# Sheet1.net
KiCad netlist of a schematic drawn in Altium Designer
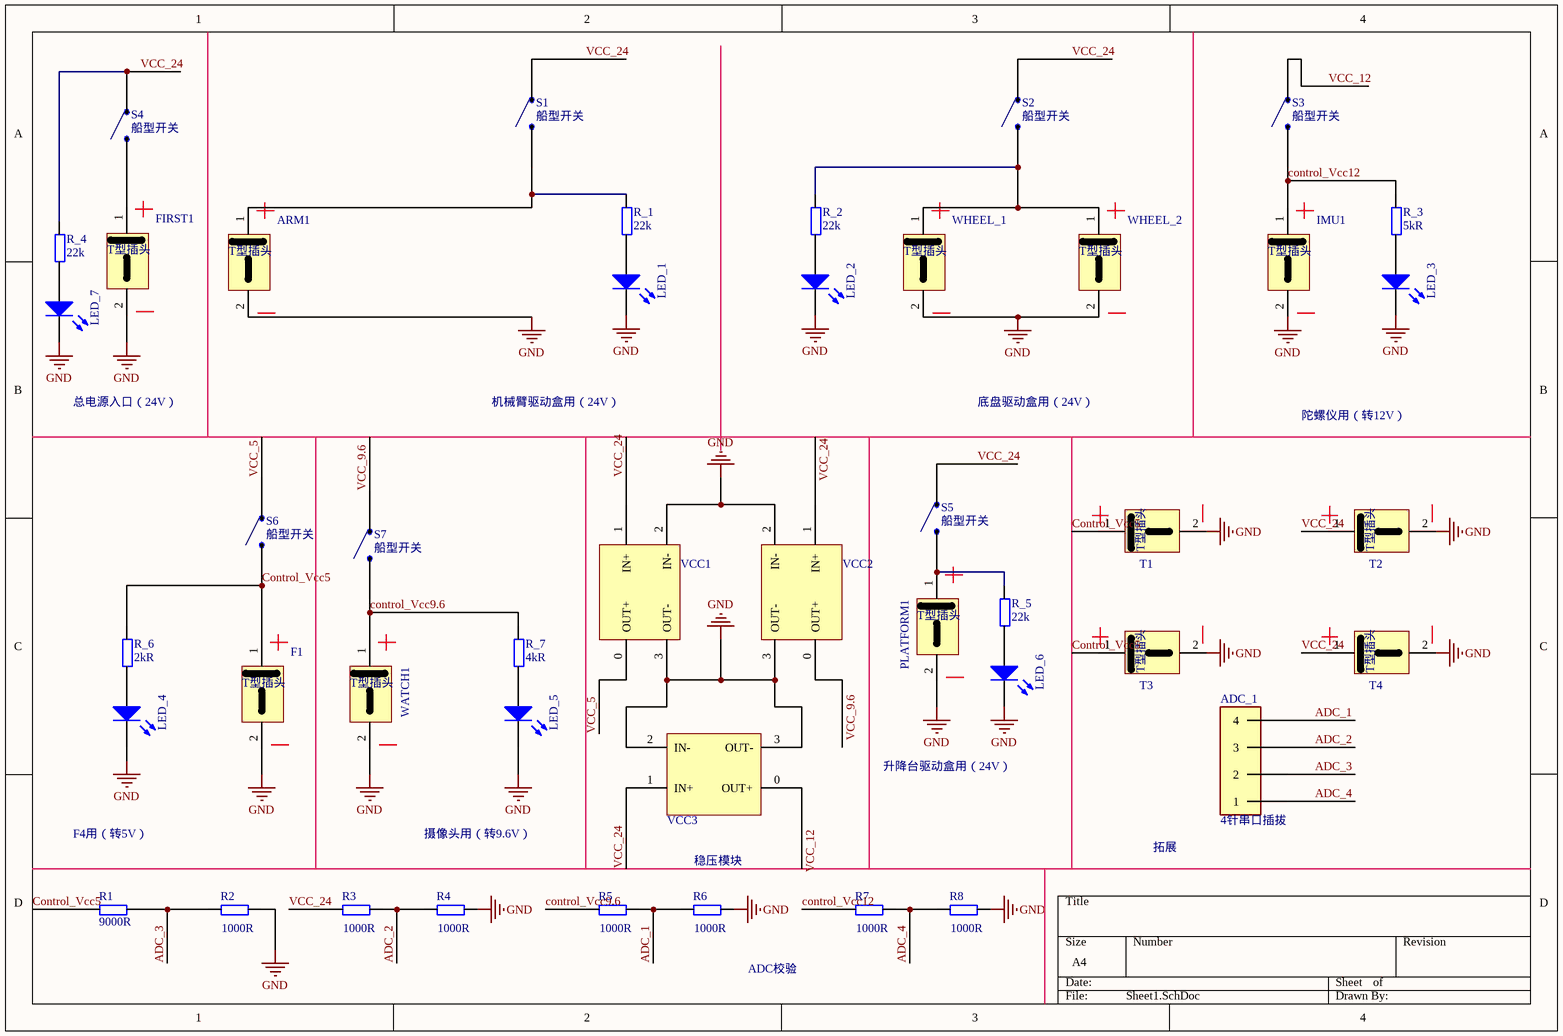
[diagram p0: Sheet1.SchDoc]

(export (version "E")
  (design (tool "Eeschema 10.0.6"))
  (components
    (comp (ref "ADC_1")
      (value "4针串口插拔")
      (footprint "HDR_4针串口插拔")
      (libsource (lib "PCB_PROJECT1") (part "4针串口插拔"))
    )
    (comp (ref "ARM1")
      (value "T型插头_WYN")
      (footprint "HDR_XT60")
      (libsource (lib "PCB_PROJECT1") (part "T型插头_WYN"))
    )
    (comp (ref "F1")
      (value "T型插头_WYN")
      (footprint "HDR_XT30")
      (libsource (lib "PCB_PROJECT1") (part "T型插头_WYN"))
    )
    (comp (ref "FIRST1")
      (value "T型插头_WYN")
      (footprint "HDR_XT60")
      (libsource (lib "PCB_PROJECT1") (part "T型插头_WYN"))
    )
    (comp (ref "IMU1")
      (value "T型插头_WYN")
      (footprint "HDR_XT30")
      (libsource (lib "PCB_PROJECT1") (part "T型插头_WYN"))
    )
    (comp (ref "LED_1")
      (value "LED")
      (footprint "ELE_SMDLED")
      (description "Typical RED, GREEN, YELLOW, AMBER GaAs LED")
      (fields (field (name "PUBLISHER") "Altium Limited"))
      (libsource (lib "PCB_PROJECT1") (part "LED2"))
    )
    (comp (ref "LED_2")
      (value "LED")
      (footprint "ELE_SMDLED")
      (description "Typical RED, GREEN, YELLOW, AMBER GaAs LED")
      (fields (field (name "PUBLISHER") "Altium Limited"))
      (libsource (lib "PCB_PROJECT1") (part "LED2"))
    )
    (comp (ref "LED_3")
      (value "LED")
      (footprint "ELE_SMDLED")
      (description "Typical RED, GREEN, YELLOW, AMBER GaAs LED")
      (fields (field (name "PUBLISHER") "Altium Limited"))
      (libsource (lib "PCB_PROJECT1") (part "LED2"))
    )
    (comp (ref "LED_4")
      (value "LED")
      (footprint "ELE_SMDLED")
      (description "Typical RED, GREEN, YELLOW, AMBER GaAs LED")
      (fields (field (name "PUBLISHER") "Altium Limited"))
      (libsource (lib "PCB_PROJECT1") (part "LED2"))
    )
    (comp (ref "LED_5")
      (value "LED")
      (footprint "ELE_SMDLED")
      (description "Typical RED, GREEN, YELLOW, AMBER GaAs LED")
      (fields (field (name "PUBLISHER") "Altium Limited"))
      (libsource (lib "PCB_PROJECT1") (part "LED2"))
    )
    (comp (ref "LED_6")
      (value "LED")
      (footprint "ELE_SMDLED")
      (description "Typical RED, GREEN, YELLOW, AMBER GaAs LED")
      (fields (field (name "PUBLISHER") "Altium Limited"))
      (libsource (lib "PCB_PROJECT1") (part "LED2"))
    )
    (comp (ref "LED_7")
      (value "LED")
      (footprint "ELE_SMDLED")
      (description "Typical RED, GREEN, YELLOW, AMBER GaAs LED")
      (fields (field (name "PUBLISHER") "Altium Limited"))
      (libsource (lib "PCB_PROJECT1") (part "LED2"))
    )
    (comp (ref "PLATFORM1")
      (value "T型插头_WYN")
      (footprint "HDR_XT60")
      (libsource (lib "PCB_PROJECT1") (part "T型插头_WYN"))
    )
    (comp (ref "R1") (value "9000R") (footprint "ELE_0603_P") (libsource (lib "PCB_PROJECT1") (part "R")))
    (comp (ref "R2") (value "1000R") (footprint "ELE_0603_P") (libsource (lib "PCB_PROJECT1") (part "R")))
    (comp (ref "R3") (value "1000R") (footprint "ELE_0603_P") (libsource (lib "PCB_PROJECT1") (part "R")))
    (comp (ref "R4") (value "1000R") (footprint "ELE_0603_P") (libsource (lib "PCB_PROJECT1") (part "R")))
    (comp (ref "R5") (value "1000R") (footprint "ELE_0603_P") (libsource (lib "PCB_PROJECT1") (part "R")))
    (comp (ref "R6") (value "1000R") (footprint "ELE_0603_P") (libsource (lib "PCB_PROJECT1") (part "R")))
    (comp (ref "R7") (value "1000R") (footprint "ELE_0603_P") (libsource (lib "PCB_PROJECT1") (part "R")))
    (comp (ref "R8") (value "1000R") (footprint "ELE_0603_P") (libsource (lib "PCB_PROJECT1") (part "R")))
    (comp (ref "R_1") (value "22k") (footprint "ELE_0603_P") (libsource (lib "PCB_PROJECT1") (part "R")))
    (comp (ref "R_2") (value "22k") (footprint "ELE_0603_P") (libsource (lib "PCB_PROJECT1") (part "R")))
    (comp (ref "R_3") (value "5kR") (footprint "ELE_0603_P") (libsource (lib "PCB_PROJECT1") (part "R")))
    (comp (ref "R_4") (value "22k") (footprint "ELE_0603_P") (libsource (lib "PCB_PROJECT1") (part "R")))
    (comp (ref "R_5") (value "22k") (footprint "ELE_0603_P") (libsource (lib "PCB_PROJECT1") (part "R")))
    (comp (ref "R_6") (value "2kR") (footprint "ELE_0603_P") (libsource (lib "PCB_PROJECT1") (part "R")))
    (comp (ref "R_7") (value "4kR") (footprint "ELE_0603_P") (libsource (lib "PCB_PROJECT1") (part "R")))
    (comp (ref "S1") (value "船型开关") (footprint "ELE_船型开关") (libsource (lib "PCB_PROJECT1") (part "船型开关")))
    (comp (ref "S2") (value "船型开关") (footprint "ELE_船型开关") (libsource (lib "PCB_PROJECT1") (part "船型开关")))
    (comp (ref "S3") (value "船型开关") (footprint "ELE_船型开关1_D") (libsource (lib "PCB_PROJECT1") (part "船型开关")))
    (comp (ref "S4") (value "船型开关") (footprint "ELE_船型开关") (libsource (lib "PCB_PROJECT1") (part "船型开关")))
    (comp (ref "S5") (value "船型开关") (footprint "ELE_船型开关") (libsource (lib "PCB_PROJECT1") (part "船型开关")))
    (comp (ref "S6") (value "船型开关") (footprint "ELE_船型开关1_D") (libsource (lib "PCB_PROJECT1") (part "船型开关")))
    (comp (ref "S7") (value "船型开关") (footprint "ELE_船型开关1_D") (libsource (lib "PCB_PROJECT1") (part "船型开关")))
    (comp (ref "T1") (value "T型插头_WYN") (footprint "HDR_XT30") (libsource (lib "") (part "T型插头_WYN_1")))
    (comp (ref "T2") (value "T型插头_WYN") (footprint "HDR_XT60") (libsource (lib "") (part "T型插头_WYN_1")))
    (comp (ref "T3") (value "T型插头_WYN") (footprint "HDR_XT30") (libsource (lib "") (part "T型插头_WYN_1")))
    (comp (ref "T4") (value "T型插头_WYN") (footprint "HDR_XT60") (libsource (lib "") (part "T型插头_WYN_1")))
    (comp (ref "VCC1")
      (value "TRANSFORM")
      (footprint "CHP_转压模块")
      (libsource (lib "PCB_PROJECT1") (part "TRANSFORM"))
    )
    (comp (ref "VCC2") (value "TRANSFORM") (footprint "CHP_转压模块") (libsource (lib "") (part "TRANSFORM_1")))
    (comp (ref "VCC3") (value "TRANSFORM") (footprint "CHP_转压模块") (libsource (lib "") (part "TRANSFORM_2")))
    (comp (ref "WATCH1")
      (value "T型插头_WYN")
      (footprint "HDR_XT30")
      (libsource (lib "PCB_PROJECT1") (part "T型插头_WYN"))
    )
    (comp (ref "WHEEL_1")
      (value "T型插头_WYN")
      (footprint "HDR_XT60")
      (libsource (lib "PCB_PROJECT1") (part "T型插头_WYN"))
    )
    (comp (ref "WHEEL_2")
      (value "T型插头_WYN")
      (footprint "HDR_XT60")
      (libsource (lib "PCB_PROJECT1") (part "T型插头_WYN"))
    )
  )
  (nets
    (net (code "1") (name "/ADC_1") (class "Default")
      (node (ref "ADC_1") (pin "4") (pinfunction "4_4") (pintype "passive"))
      (node (ref "R5") (pin "2") (pintype "passive"))
      (node (ref "R6") (pin "1") (pintype "passive"))
    )
    (net (code "2") (name "/ADC_2") (class "Default")
      (node (ref "ADC_1") (pin "3") (pinfunction "3_3") (pintype "passive"))
      (node (ref "R3") (pin "2") (pintype "passive"))
      (node (ref "R4") (pin "1") (pintype "passive"))
    )
    (net (code "3") (name "/ADC_3") (class "Default")
      (node (ref "ADC_1") (pin "2") (pinfunction "2_2") (pintype "passive"))
      (node (ref "R1") (pin "2") (pintype "passive"))
      (node (ref "R2") (pin "1") (pintype "passive"))
    )
    (net (code "4") (name "/ADC_4") (class "Default")
      (node (ref "ADC_1") (pin "1") (pinfunction "1_1") (pintype "passive"))
      (node (ref "R7") (pin "2") (pintype "passive"))
      (node (ref "R8") (pin "1") (pintype "passive"))
    )
    (net (code "5") (name "/Control_Vcc5") (class "Default")
      (node (ref "F1") (pin "1") (pinfunction "1_1") (pintype "passive"))
      (node (ref "R1") (pin "1") (pintype "passive"))
      (node (ref "R_6") (pin "2") (pintype "passive"))
      (node (ref "S6") (pin "1") (pinfunction "1_1") (pintype "passive"))
      (node (ref "T1") (pin "1") (pinfunction "1_1") (pintype "passive"))
      (node (ref "T3") (pin "1") (pinfunction "1_1") (pintype "passive"))
    )
    (net (code "6") (name "/VCC_5") (class "Default")
      (node (ref "S6") (pin "2") (pinfunction "2_2") (pintype "passive"))
      (node (ref "VCC1") (pin "0") (pinfunction "OUT+_0") (pintype "passive"))
    )
    (net (code "7") (name "/VCC_9.6") (class "Default")
      (node (ref "S7") (pin "2") (pinfunction "2_2") (pintype "passive"))
      (node (ref "VCC2") (pin "0") (pinfunction "OUT+_0") (pintype "passive"))
    )
    (net (code "8") (name "/VCC_12") (class "Default")
      (node (ref "S3") (pin "2") (pinfunction "2_2") (pintype "passive"))
      (node (ref "VCC3") (pin "0") (pinfunction "OUT+_0") (pintype "passive"))
    )
    (net (code "9") (name "/VCC_24") (class "Default")
      (node (ref "R3") (pin "1") (pintype "passive"))
      (node (ref "R_4") (pin "2") (pintype "passive"))
      (node (ref "S1") (pin "2") (pinfunction "2_2") (pintype "passive"))
      (node (ref "S2") (pin "2") (pinfunction "2_2") (pintype "passive"))
      (node (ref "S4") (pin "2") (pinfunction "2_2") (pintype "passive"))
      (node (ref "S5") (pin "2") (pinfunction "2_2") (pintype "passive"))
      (node (ref "T2") (pin "1") (pinfunction "1_1") (pintype "passive"))
      (node (ref "T4") (pin "1") (pinfunction "1_1") (pintype "passive"))
      (node (ref "VCC1") (pin "1") (pinfunction "IN+_1") (pintype "passive"))
      (node (ref "VCC2") (pin "1") (pinfunction "IN+_1") (pintype "passive"))
      (node (ref "VCC3") (pin "1") (pinfunction "IN+_1") (pintype "passive"))
    )
    (net (code "10") (name "/control_Vcc9.6") (class "Default")
      (node (ref "R5") (pin "1") (pintype "passive"))
      (node (ref "R_7") (pin "2") (pintype "passive"))
      (node (ref "S7") (pin "1") (pinfunction "1_1") (pintype "passive"))
      (node (ref "WATCH1") (pin "1") (pinfunction "1_1") (pintype "passive"))
    )
    (net (code "11") (name "/control_Vcc12") (class "Default")
      (node (ref "IMU1") (pin "1") (pinfunction "1_1") (pintype "passive"))
      (node (ref "R7") (pin "1") (pintype "passive"))
      (node (ref "R_3") (pin "2") (pintype "passive"))
      (node (ref "S3") (pin "1") (pinfunction "1_1") (pintype "passive"))
    )
    (net (code "12") (name "GND") (class "Default")
      (node (ref "ARM1") (pin "2") (pinfunction "2_2") (pintype "passive"))
      (node (ref "F1") (pin "2") (pinfunction "2_2") (pintype "passive"))
      (node (ref "FIRST1") (pin "2") (pinfunction "2_2") (pintype "passive"))
      (node (ref "IMU1") (pin "2") (pinfunction "2_2") (pintype "passive"))
      (node (ref "LED_1") (pin "2") (pinfunction "K_2") (pintype "passive"))
      (node (ref "LED_2") (pin "2") (pinfunction "K_2") (pintype "passive"))
      (node (ref "LED_3") (pin "2") (pinfunction "K_2") (pintype "passive"))
      (node (ref "LED_4") (pin "2") (pinfunction "K_2") (pintype "passive"))
      (node (ref "LED_5") (pin "2") (pinfunction "K_2") (pintype "passive"))
      (node (ref "LED_6") (pin "2") (pinfunction "K_2") (pintype "passive"))
      (node (ref "LED_7") (pin "2") (pinfunction "K_2") (pintype "passive"))
      (node (ref "PLATFORM1") (pin "2") (pinfunction "2_2") (pintype "passive"))
      (node (ref "R2") (pin "2") (pintype "passive"))
      (node (ref "R4") (pin "2") (pintype "passive"))
      (node (ref "R6") (pin "2") (pintype "passive"))
      (node (ref "R8") (pin "2") (pintype "passive"))
      (node (ref "T1") (pin "2") (pinfunction "2_2") (pintype "passive"))
      (node (ref "T2") (pin "2") (pinfunction "2_2") (pintype "passive"))
      (node (ref "T3") (pin "2") (pinfunction "2_2") (pintype "passive"))
      (node (ref "T4") (pin "2") (pinfunction "2_2") (pintype "passive"))
      (node (ref "VCC1") (pin "2") (pinfunction "IN-_2") (pintype "passive"))
      (node (ref "VCC1") (pin "3") (pinfunction "OUT-_3") (pintype "passive"))
      (node (ref "VCC2") (pin "2") (pinfunction "IN-_2") (pintype "passive"))
      (node (ref "VCC2") (pin "3") (pinfunction "OUT-_3") (pintype "passive"))
      (node (ref "VCC3") (pin "2") (pinfunction "IN-_2") (pintype "passive"))
      (node (ref "VCC3") (pin "3") (pinfunction "OUT-_3") (pintype "passive"))
      (node (ref "WATCH1") (pin "2") (pinfunction "2_2") (pintype "passive"))
      (node (ref "WHEEL_1") (pin "2") (pinfunction "2_2") (pintype "passive"))
      (node (ref "WHEEL_2") (pin "2") (pinfunction "2_2") (pintype "passive"))
    )
    (net (code "13") (name "Net-(ARM1-Pad1)") (class "Default")
      (node (ref "ARM1") (pin "1") (pinfunction "1_1") (pintype "passive"))
      (node (ref "R_1") (pin "2") (pintype "passive"))
      (node (ref "S1") (pin "1") (pinfunction "1_1") (pintype "passive"))
    )
    (net (code "14") (name "Net-(FIRST1-Pad1)") (class "Default")
      (node (ref "FIRST1") (pin "1") (pinfunction "1_1") (pintype "passive"))
      (node (ref "S4") (pin "1") (pinfunction "1_1") (pintype "passive"))
    )
    (net (code "15") (name "Net-(LED_1-A)") (class "Default")
      (node (ref "LED_1") (pin "1") (pinfunction "A_1") (pintype "passive"))
      (node (ref "R_1") (pin "1") (pintype "passive"))
    )
    (net (code "16") (name "Net-(LED_2-A)") (class "Default")
      (node (ref "LED_2") (pin "1") (pinfunction "A_1") (pintype "passive"))
      (node (ref "R_2") (pin "1") (pintype "passive"))
    )
    (net (code "17") (name "Net-(LED_3-A)") (class "Default")
      (node (ref "LED_3") (pin "1") (pinfunction "A_1") (pintype "passive"))
      (node (ref "R_3") (pin "1") (pintype "passive"))
    )
    (net (code "18") (name "Net-(LED_4-A)") (class "Default")
      (node (ref "LED_4") (pin "1") (pinfunction "A_1") (pintype "passive"))
      (node (ref "R_6") (pin "1") (pintype "passive"))
    )
    (net (code "19") (name "Net-(LED_5-A)") (class "Default")
      (node (ref "LED_5") (pin "1") (pinfunction "A_1") (pintype "passive"))
      (node (ref "R_7") (pin "1") (pintype "passive"))
    )
    (net (code "20") (name "Net-(LED_6-A)") (class "Default")
      (node (ref "LED_6") (pin "1") (pinfunction "A_1") (pintype "passive"))
      (node (ref "R_5") (pin "1") (pintype "passive"))
    )
    (net (code "21") (name "Net-(LED_7-A)") (class "Default")
      (node (ref "LED_7") (pin "1") (pinfunction "A_1") (pintype "passive"))
      (node (ref "R_4") (pin "1") (pintype "passive"))
    )
    (net (code "22") (name "Net-(PLATFORM1-Pad1)") (class "Default")
      (node (ref "PLATFORM1") (pin "1") (pinfunction "1_1") (pintype "passive"))
      (node (ref "R_5") (pin "2") (pintype "passive"))
      (node (ref "S5") (pin "1") (pinfunction "1_1") (pintype "passive"))
    )
    (net (code "23") (name "Net-(R_2-Pad2)") (class "Default")
      (node (ref "R_2") (pin "2") (pintype "passive"))
      (node (ref "S2") (pin "1") (pinfunction "1_1") (pintype "passive"))
      (node (ref "WHEEL_1") (pin "1") (pinfunction "1_1") (pintype "passive"))
      (node (ref "WHEEL_2") (pin "1") (pinfunction "1_1") (pintype "passive"))
    )
  )
)
